# Neve.net
KiCad netlist of a schematic drawn in EAGLE
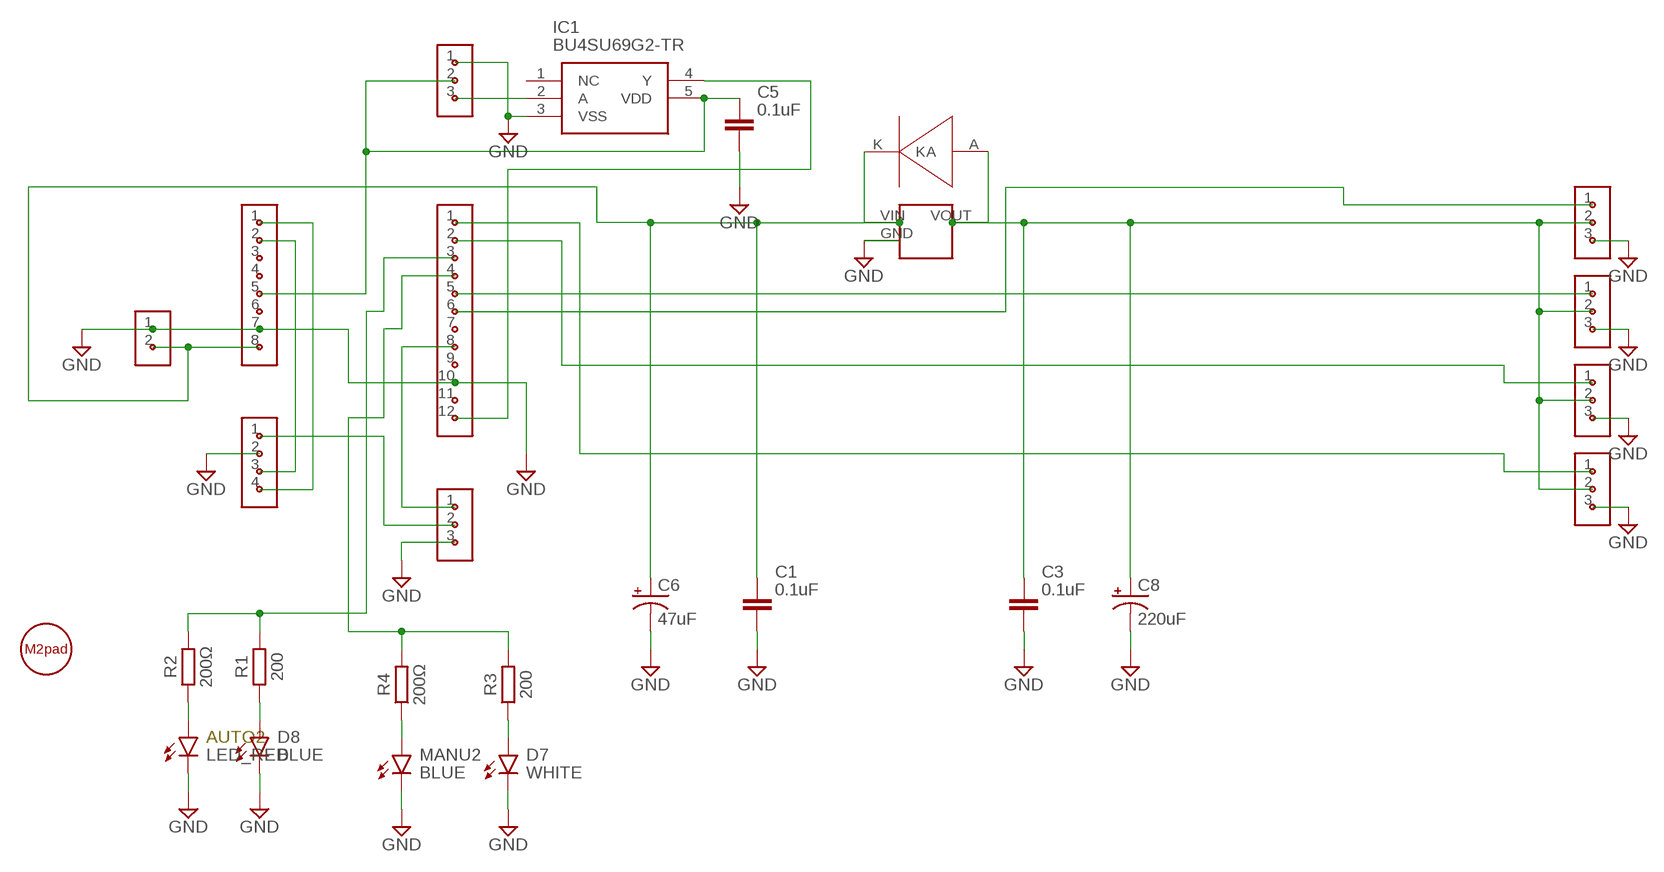
[diagram p0: schematic, sheet 1]

(export (version "E")
  (design (tool "Eeschema 10.0.6"))
  (components
    (comp (ref "AUTO2")
      (value "LED_RED")
      (footprint "eagle-import:LEDC1608X65N_RND-R")
      (libsource (lib "eagle-import") (part "CHIP-ROUND-R_0603"))
    )
    (comp (ref "C1")
      (value "0.1uF")
      (footprint "eagle-import:CAPC2012X110")
      (libsource (lib "eagle-import") (part "CCHIP-0805(2012-METRIC)_"))
    )
    (comp (ref "C3")
      (value "0.1uF")
      (footprint "eagle-import:CAPC2012X110")
      (libsource (lib "eagle-import") (part "CCHIP-0805(2012-METRIC)_"))
    )
    (comp (ref "C5")
      (value "0.1uF")
      (footprint "eagle-import:CAPC2012X110")
      (libsource (lib "eagle-import") (part "CCHIP-0805(2012-METRIC)_"))
    )
    (comp (ref "C6")
      (value "47uF")
      (footprint "eagle-import:153CLV-0605")
      (libsource (lib "eagle-import") (part "CPOL-US153CLV-0605"))
    )
    (comp (ref "C8")
      (value "220uF")
      (footprint "eagle-import:153CLV-0605")
      (libsource (lib "eagle-import") (part "CPOL-US153CLV-0605"))
    )
    (comp (ref "D7")
      (value "WHITE")
      (footprint "eagle-import:LEDC1608X65N_RND-R")
      (libsource (lib "eagle-import") (part "CHIP-ROUND-R_0603"))
    )
    (comp (ref "D8")
      (value "BLUE")
      (footprint "eagle-import:LEDC1608X65N_RND-R")
      (libsource (lib "eagle-import") (part "CHIP-ROUND-R_0603"))
    )
    (comp (ref "DIODE1")
      (value "CRG01")
      (footprint "eagle-import:CRG01")
      (libsource (lib "eagle-import") (part "CRG01"))
    )
    (comp (ref "IC1")
      (value "BU4SU69G2-TR")
      (footprint "eagle-import:SOT95P280X125-5N")
      (fields (field (name "RS_PART_NUMBER") "1682415P"))
      (libsource (lib "eagle-import") (part "BU4SU69G2-TR"))
    )
    (comp (ref "JP1")
      (value "PIN_1X3")
      (footprint "eagle-import:PIN_1X3")
      (libsource (lib "eagle-import") (part "PIN_1X3"))
    )
    (comp (ref "JP2")
      (value "PIN_1X3")
      (footprint "eagle-import:PIN_1X3")
      (libsource (lib "eagle-import") (part "PIN_1X3"))
    )
    (comp (ref "JP3")
      (value "PIN_1X3")
      (footprint "eagle-import:PIN_1X3")
      (libsource (lib "eagle-import") (part "PIN_1X3"))
    )
    (comp (ref "JP4")
      (value "PIN_1X3")
      (footprint "eagle-import:PIN_1X3")
      (libsource (lib "eagle-import") (part "PIN_1X3"))
    )
    (comp (ref "JP5")
      (value "PIN_1X3")
      (footprint "eagle-import:PIN_1X3")
      (libsource (lib "eagle-import") (part "PIN_1X3"))
    )
    (comp (ref "JP6")
      (value "PIN_1X4")
      (footprint "eagle-import:PIN_1X4")
      (libsource (lib "eagle-import") (part "PIN_1X4"))
    )
    (comp (ref "JP7")
      (value "PIN_1X2")
      (footprint "eagle-import:PIN_1X2")
      (libsource (lib "eagle-import") (part "PIN_1X2"))
    )
    (comp (ref "JP8")
      (value "PIN_1X3")
      (footprint "eagle-import:PIN_1X3")
      (libsource (lib "eagle-import") (part "PIN_1X3"))
    )
    (comp (ref "JP9")
      (value "PIN_1X12")
      (footprint "eagle-import:PIN_1X12")
      (libsource (lib "eagle-import") (part "PIN_1X12"))
    )
    (comp (ref "JP10")
      (value "PIN_1X8")
      (footprint "eagle-import:PIN_1X8")
      (libsource (lib "eagle-import") (part "PIN_1X8"))
    )
    (comp (ref "MANU2")
      (value "BLUE")
      (footprint "eagle-import:LEDC1608X65N_RND-R")
      (libsource (lib "eagle-import") (part "CHIP-ROUND-R_0603"))
    )
    (comp (ref "R1")
      (value "200")
      (footprint "eagle-import:RESC2012X65")
      (libsource (lib "eagle-import") (part "RCHIP-0805(2012-METRIC)_"))
    )
    (comp (ref "R2")
      (value "200Ω")
      (footprint "eagle-import:RESC2012X65")
      (libsource (lib "eagle-import") (part "RCHIP-0805(2012-METRIC)_"))
    )
    (comp (ref "R3")
      (value "200")
      (footprint "eagle-import:RESC2012X65")
      (libsource (lib "eagle-import") (part "RCHIP-0805(2012-METRIC)_"))
    )
    (comp (ref "R4")
      (value "200Ω")
      (footprint "eagle-import:RESC2012X65")
      (libsource (lib "eagle-import") (part "RCHIP-0805(2012-METRIC)_"))
    )
    (comp (ref "RG1")
      (value "NJM7805SDL1")
      (footprint "eagle-import:NJM7805SDL1")
      (libsource (lib "eagle-import") (part "NJM7805SDL1"))
    )
    (comp (ref "U$1")
      (value "M2PAD")
      (footprint "eagle-import:M2PAD")
      (libsource (lib "eagle-import") (part "M2PAD"))
    )
  )
  (nets
    (net (code "1") (name "GND") (class "Default")
      (node (ref "AUTO2") (pin "C") (pinfunction "C_C") (pintype "passive"))
      (node (ref "C1") (pin "2") (pinfunction "2_2") (pintype "passive"))
      (node (ref "C3") (pin "2") (pinfunction "2_2") (pintype "passive"))
      (node (ref "C5") (pin "2") (pinfunction "2_2") (pintype "passive"))
      (node (ref "C6") (pin "-") (pinfunction "-_-") (pintype "passive"))
      (node (ref "C8") (pin "-") (pinfunction "-_-") (pintype "passive"))
      (node (ref "D7") (pin "C") (pinfunction "C_C") (pintype "passive"))
      (node (ref "D8") (pin "C") (pinfunction "C_C") (pintype "passive"))
      (node (ref "IC1") (pin "3") (pinfunction "VSS_3") (pintype "bidirectional"))
      (node (ref "JP1") (pin "3") (pinfunction "3_3") (pintype "bidirectional"))
      (node (ref "JP10") (pin "7") (pinfunction "7_7") (pintype "bidirectional"))
      (node (ref "JP2") (pin "3") (pinfunction "3_3") (pintype "bidirectional"))
      (node (ref "JP3") (pin "3") (pinfunction "3_3") (pintype "bidirectional"))
      (node (ref "JP4") (pin "3") (pinfunction "3_3") (pintype "bidirectional"))
      (node (ref "JP5") (pin "3") (pinfunction "3_3") (pintype "bidirectional"))
      (node (ref "JP6") (pin "2") (pinfunction "2_2") (pintype "bidirectional"))
      (node (ref "JP7") (pin "1") (pinfunction "1_1") (pintype "bidirectional"))
      (node (ref "JP8") (pin "1") (pinfunction "1_1") (pintype "bidirectional"))
      (node (ref "JP9") (pin "10") (pinfunction "10_10") (pintype "bidirectional"))
      (node (ref "MANU2") (pin "C") (pinfunction "C_C") (pintype "passive"))
      (node (ref "RG1") (pin "GND") (pinfunction "GND_GND") (pintype "bidirectional"))
    )
    (net (code "2") (name "Net-(AUTO2-PadA)") (class "Default")
      (node (ref "AUTO2") (pin "A") (pinfunction "A_A") (pintype "passive"))
      (node (ref "R2") (pin "1") (pinfunction "1_1") (pintype "passive"))
    )
    (net (code "3") (name "Net-(C1-Pad1)") (class "Default")
      (node (ref "C1") (pin "1") (pinfunction "1_1") (pintype "passive"))
      (node (ref "C6") (pin "+") (pinfunction "+_+") (pintype "passive"))
      (node (ref "DIODE1") (pin "K") (pinfunction "K_K") (pintype "bidirectional"))
      (node (ref "JP10") (pin "8") (pinfunction "8_8") (pintype "bidirectional"))
      (node (ref "JP7") (pin "2") (pinfunction "2_2") (pintype "bidirectional"))
      (node (ref "RG1") (pin "VIN") (pinfunction "VIN_VIN") (pintype "bidirectional"))
    )
    (net (code "4") (name "Net-(C3-Pad1)") (class "Default")
      (node (ref "C3") (pin "1") (pinfunction "1_1") (pintype "passive"))
      (node (ref "C8") (pin "+") (pinfunction "+_+") (pintype "passive"))
      (node (ref "DIODE1") (pin "A") (pinfunction "A_A") (pintype "bidirectional"))
      (node (ref "JP1") (pin "2") (pinfunction "2_2") (pintype "bidirectional"))
      (node (ref "JP2") (pin "2") (pinfunction "2_2") (pintype "bidirectional"))
      (node (ref "JP3") (pin "2") (pinfunction "2_2") (pintype "bidirectional"))
      (node (ref "JP4") (pin "2") (pinfunction "2_2") (pintype "bidirectional"))
      (node (ref "RG1") (pin "VOUT") (pinfunction "VOUT_VOUT") (pintype "bidirectional"))
    )
    (net (code "5") (name "Net-(D7-PadA)") (class "Default")
      (node (ref "D7") (pin "A") (pinfunction "A_A") (pintype "passive"))
      (node (ref "R3") (pin "1") (pinfunction "1_1") (pintype "passive"))
    )
    (net (code "6") (name "Net-(D8-PadA)") (class "Default")
      (node (ref "D8") (pin "A") (pinfunction "A_A") (pintype "passive"))
      (node (ref "R1") (pin "1") (pinfunction "1_1") (pintype "passive"))
    )
    (net (code "7") (name "Net-(IC1-A)") (class "Default")
      (node (ref "IC1") (pin "2") (pinfunction "A_2") (pintype "bidirectional"))
      (node (ref "JP8") (pin "3") (pinfunction "3_3") (pintype "bidirectional"))
    )
    (net (code "8") (name "Net-(IC1-VDD)") (class "Default")
      (node (ref "C5") (pin "1") (pinfunction "1_1") (pintype "passive"))
      (node (ref "IC1") (pin "5") (pinfunction "VDD_5") (pintype "bidirectional"))
      (node (ref "JP10") (pin "5") (pinfunction "5_5") (pintype "bidirectional"))
      (node (ref "JP8") (pin "2") (pinfunction "2_2") (pintype "bidirectional"))
    )
    (net (code "9") (name "Net-(IC1-Y)") (class "Default")
      (node (ref "IC1") (pin "4") (pinfunction "Y_4") (pintype "bidirectional"))
      (node (ref "JP9") (pin "12") (pinfunction "12_12") (pintype "bidirectional"))
    )
    (net (code "10") (name "Net-(JP1-Pad1)") (class "Default")
      (node (ref "JP1") (pin "1") (pinfunction "1_1") (pintype "bidirectional"))
      (node (ref "JP9") (pin "6") (pinfunction "6_6") (pintype "bidirectional"))
    )
    (net (code "11") (name "Net-(JP2-Pad1)") (class "Default")
      (node (ref "JP2") (pin "1") (pinfunction "1_1") (pintype "bidirectional"))
      (node (ref "JP9") (pin "5") (pinfunction "5_5") (pintype "bidirectional"))
    )
    (net (code "12") (name "Net-(JP3-Pad1)") (class "Default")
      (node (ref "JP3") (pin "1") (pinfunction "1_1") (pintype "bidirectional"))
      (node (ref "JP9") (pin "2") (pinfunction "2_2") (pintype "bidirectional"))
    )
    (net (code "13") (name "Net-(JP4-Pad1)") (class "Default")
      (node (ref "JP4") (pin "1") (pinfunction "1_1") (pintype "bidirectional"))
      (node (ref "JP9") (pin "1") (pinfunction "1_1") (pintype "bidirectional"))
    )
    (net (code "14") (name "Net-(JP5-Pad1)") (class "Default")
      (node (ref "JP5") (pin "1") (pinfunction "1_1") (pintype "bidirectional"))
      (node (ref "JP9") (pin "8") (pinfunction "8_8") (pintype "bidirectional"))
    )
    (net (code "15") (name "Net-(JP5-Pad2)") (class "Default")
      (node (ref "JP5") (pin "2") (pinfunction "2_2") (pintype "bidirectional"))
      (node (ref "JP6") (pin "1") (pinfunction "1_1") (pintype "bidirectional"))
    )
    (net (code "16") (name "Net-(JP9-Pad3)") (class "Default")
      (node (ref "JP9") (pin "3") (pinfunction "3_3") (pintype "bidirectional"))
      (node (ref "R1") (pin "2") (pinfunction "2_2") (pintype "passive"))
      (node (ref "R2") (pin "2") (pinfunction "2_2") (pintype "passive"))
    )
    (net (code "17") (name "Net-(JP9-Pad4)") (class "Default")
      (node (ref "JP9") (pin "4") (pinfunction "4_4") (pintype "bidirectional"))
      (node (ref "R3") (pin "2") (pinfunction "2_2") (pintype "passive"))
      (node (ref "R4") (pin "2") (pinfunction "2_2") (pintype "passive"))
    )
    (net (code "18") (name "Net-(JP10-Pad1)") (class "Default")
      (node (ref "JP10") (pin "1") (pinfunction "1_1") (pintype "bidirectional"))
      (node (ref "JP6") (pin "4") (pinfunction "4_4") (pintype "bidirectional"))
    )
    (net (code "19") (name "Net-(JP10-Pad2)") (class "Default")
      (node (ref "JP10") (pin "2") (pinfunction "2_2") (pintype "bidirectional"))
      (node (ref "JP6") (pin "3") (pinfunction "3_3") (pintype "bidirectional"))
    )
    (net (code "20") (name "Net-(MANU2-PadA)") (class "Default")
      (node (ref "MANU2") (pin "A") (pinfunction "A_A") (pintype "passive"))
      (node (ref "R4") (pin "1") (pinfunction "1_1") (pintype "passive"))
    )
    (net (code "21") (name "unconnected-(IC1-NC-Pad1)") (class "Default")
      (node (ref "IC1") (pin "1") (pinfunction "NC_1") (pintype "no_connect"))
    )
    (net (code "22") (name "unconnected-(JP9-Pad7)") (class "Default")
      (node (ref "JP9") (pin "7") (pinfunction "7_7") (pintype "bidirectional"))
    )
    (net (code "23") (name "unconnected-(JP9-Pad9)") (class "Default")
      (node (ref "JP9") (pin "9") (pinfunction "9_9") (pintype "bidirectional"))
    )
    (net (code "24") (name "unconnected-(JP9-Pad11)") (class "Default")
      (node (ref "JP9") (pin "11") (pinfunction "11_11") (pintype "bidirectional"))
    )
    (net (code "25") (name "unconnected-(JP10-Pad3)") (class "Default")
      (node (ref "JP10") (pin "3") (pinfunction "3_3") (pintype "bidirectional"))
    )
    (net (code "26") (name "unconnected-(JP10-Pad4)") (class "Default")
      (node (ref "JP10") (pin "4") (pinfunction "4_4") (pintype "bidirectional"))
    )
    (net (code "27") (name "unconnected-(JP10-Pad6)") (class "Default")
      (node (ref "JP10") (pin "6") (pinfunction "6_6") (pintype "bidirectional"))
    )
  )
)
